# Main.net
KiCad netlist of a schematic drawn in Altium Designer
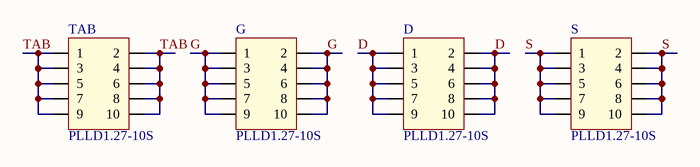
[diagram p0: Main.SchDoc]

(export (version "E")
  (design (tool "Eeschema 10.0.6"))
  (components
    (comp (ref "D")
      (value "PLLD1.27-10S")
      (footprint "PLLD1.27-10S")
      (libsource (lib "Connectors") (part "PLLD1.27-10S"))
    )
    (comp (ref "G")
      (value "PLLD1.27-10S")
      (footprint "PLLD1.27-10S")
      (libsource (lib "Connectors") (part "PLLD1.27-10S"))
    )
    (comp (ref "S")
      (value "PLLD1.27-10S")
      (footprint "PLLD1.27-10S")
      (libsource (lib "Connectors") (part "PLLD1.27-10S"))
    )
    (comp (ref "TAB")
      (value "PLLD1.27-10S")
      (footprint "PLLD1.27-10S")
      (libsource (lib "Connectors") (part "PLLD1.27-10S"))
    )
  )
  (nets
    (net (code "1") (name "/D") (class "Default")
      (node (ref "D") (pin "1") (pinfunction "1_1") (pintype "passive"))
      (node (ref "D") (pin "10") (pinfunction "10_10") (pintype "passive"))
      (node (ref "D") (pin "2") (pinfunction "2_2") (pintype "passive"))
      (node (ref "D") (pin "3") (pinfunction "3_3") (pintype "passive"))
      (node (ref "D") (pin "4") (pinfunction "4_4") (pintype "passive"))
      (node (ref "D") (pin "5") (pinfunction "5_5") (pintype "passive"))
      (node (ref "D") (pin "6") (pinfunction "6_6") (pintype "passive"))
      (node (ref "D") (pin "7") (pinfunction "7_7") (pintype "passive"))
      (node (ref "D") (pin "8") (pinfunction "8_8") (pintype "passive"))
      (node (ref "D") (pin "9") (pinfunction "9_9") (pintype "passive"))
    )
    (net (code "2") (name "/G") (class "Default")
      (node (ref "G") (pin "1") (pinfunction "1_1") (pintype "passive"))
      (node (ref "G") (pin "10") (pinfunction "10_10") (pintype "passive"))
      (node (ref "G") (pin "2") (pinfunction "2_2") (pintype "passive"))
      (node (ref "G") (pin "3") (pinfunction "3_3") (pintype "passive"))
      (node (ref "G") (pin "4") (pinfunction "4_4") (pintype "passive"))
      (node (ref "G") (pin "5") (pinfunction "5_5") (pintype "passive"))
      (node (ref "G") (pin "6") (pinfunction "6_6") (pintype "passive"))
      (node (ref "G") (pin "7") (pinfunction "7_7") (pintype "passive"))
      (node (ref "G") (pin "8") (pinfunction "8_8") (pintype "passive"))
      (node (ref "G") (pin "9") (pinfunction "9_9") (pintype "passive"))
    )
    (net (code "3") (name "/S") (class "Default")
      (node (ref "S") (pin "1") (pinfunction "1_1") (pintype "passive"))
      (node (ref "S") (pin "10") (pinfunction "10_10") (pintype "passive"))
      (node (ref "S") (pin "2") (pinfunction "2_2") (pintype "passive"))
      (node (ref "S") (pin "3") (pinfunction "3_3") (pintype "passive"))
      (node (ref "S") (pin "4") (pinfunction "4_4") (pintype "passive"))
      (node (ref "S") (pin "5") (pinfunction "5_5") (pintype "passive"))
      (node (ref "S") (pin "6") (pinfunction "6_6") (pintype "passive"))
      (node (ref "S") (pin "7") (pinfunction "7_7") (pintype "passive"))
      (node (ref "S") (pin "8") (pinfunction "8_8") (pintype "passive"))
      (node (ref "S") (pin "9") (pinfunction "9_9") (pintype "passive"))
    )
    (net (code "4") (name "/TAB") (class "Default")
      (node (ref "TAB") (pin "1") (pinfunction "1_1") (pintype "passive"))
      (node (ref "TAB") (pin "10") (pinfunction "10_10") (pintype "passive"))
      (node (ref "TAB") (pin "2") (pinfunction "2_2") (pintype "passive"))
      (node (ref "TAB") (pin "3") (pinfunction "3_3") (pintype "passive"))
      (node (ref "TAB") (pin "4") (pinfunction "4_4") (pintype "passive"))
      (node (ref "TAB") (pin "5") (pinfunction "5_5") (pintype "passive"))
      (node (ref "TAB") (pin "6") (pinfunction "6_6") (pintype "passive"))
      (node (ref "TAB") (pin "7") (pinfunction "7_7") (pintype "passive"))
      (node (ref "TAB") (pin "8") (pinfunction "8_8") (pintype "passive"))
      (node (ref "TAB") (pin "9") (pinfunction "9_9") (pintype "passive"))
    )
  )
)
